# STMF4VE.net
KiCad netlist of a schematic drawn in Altium Designer
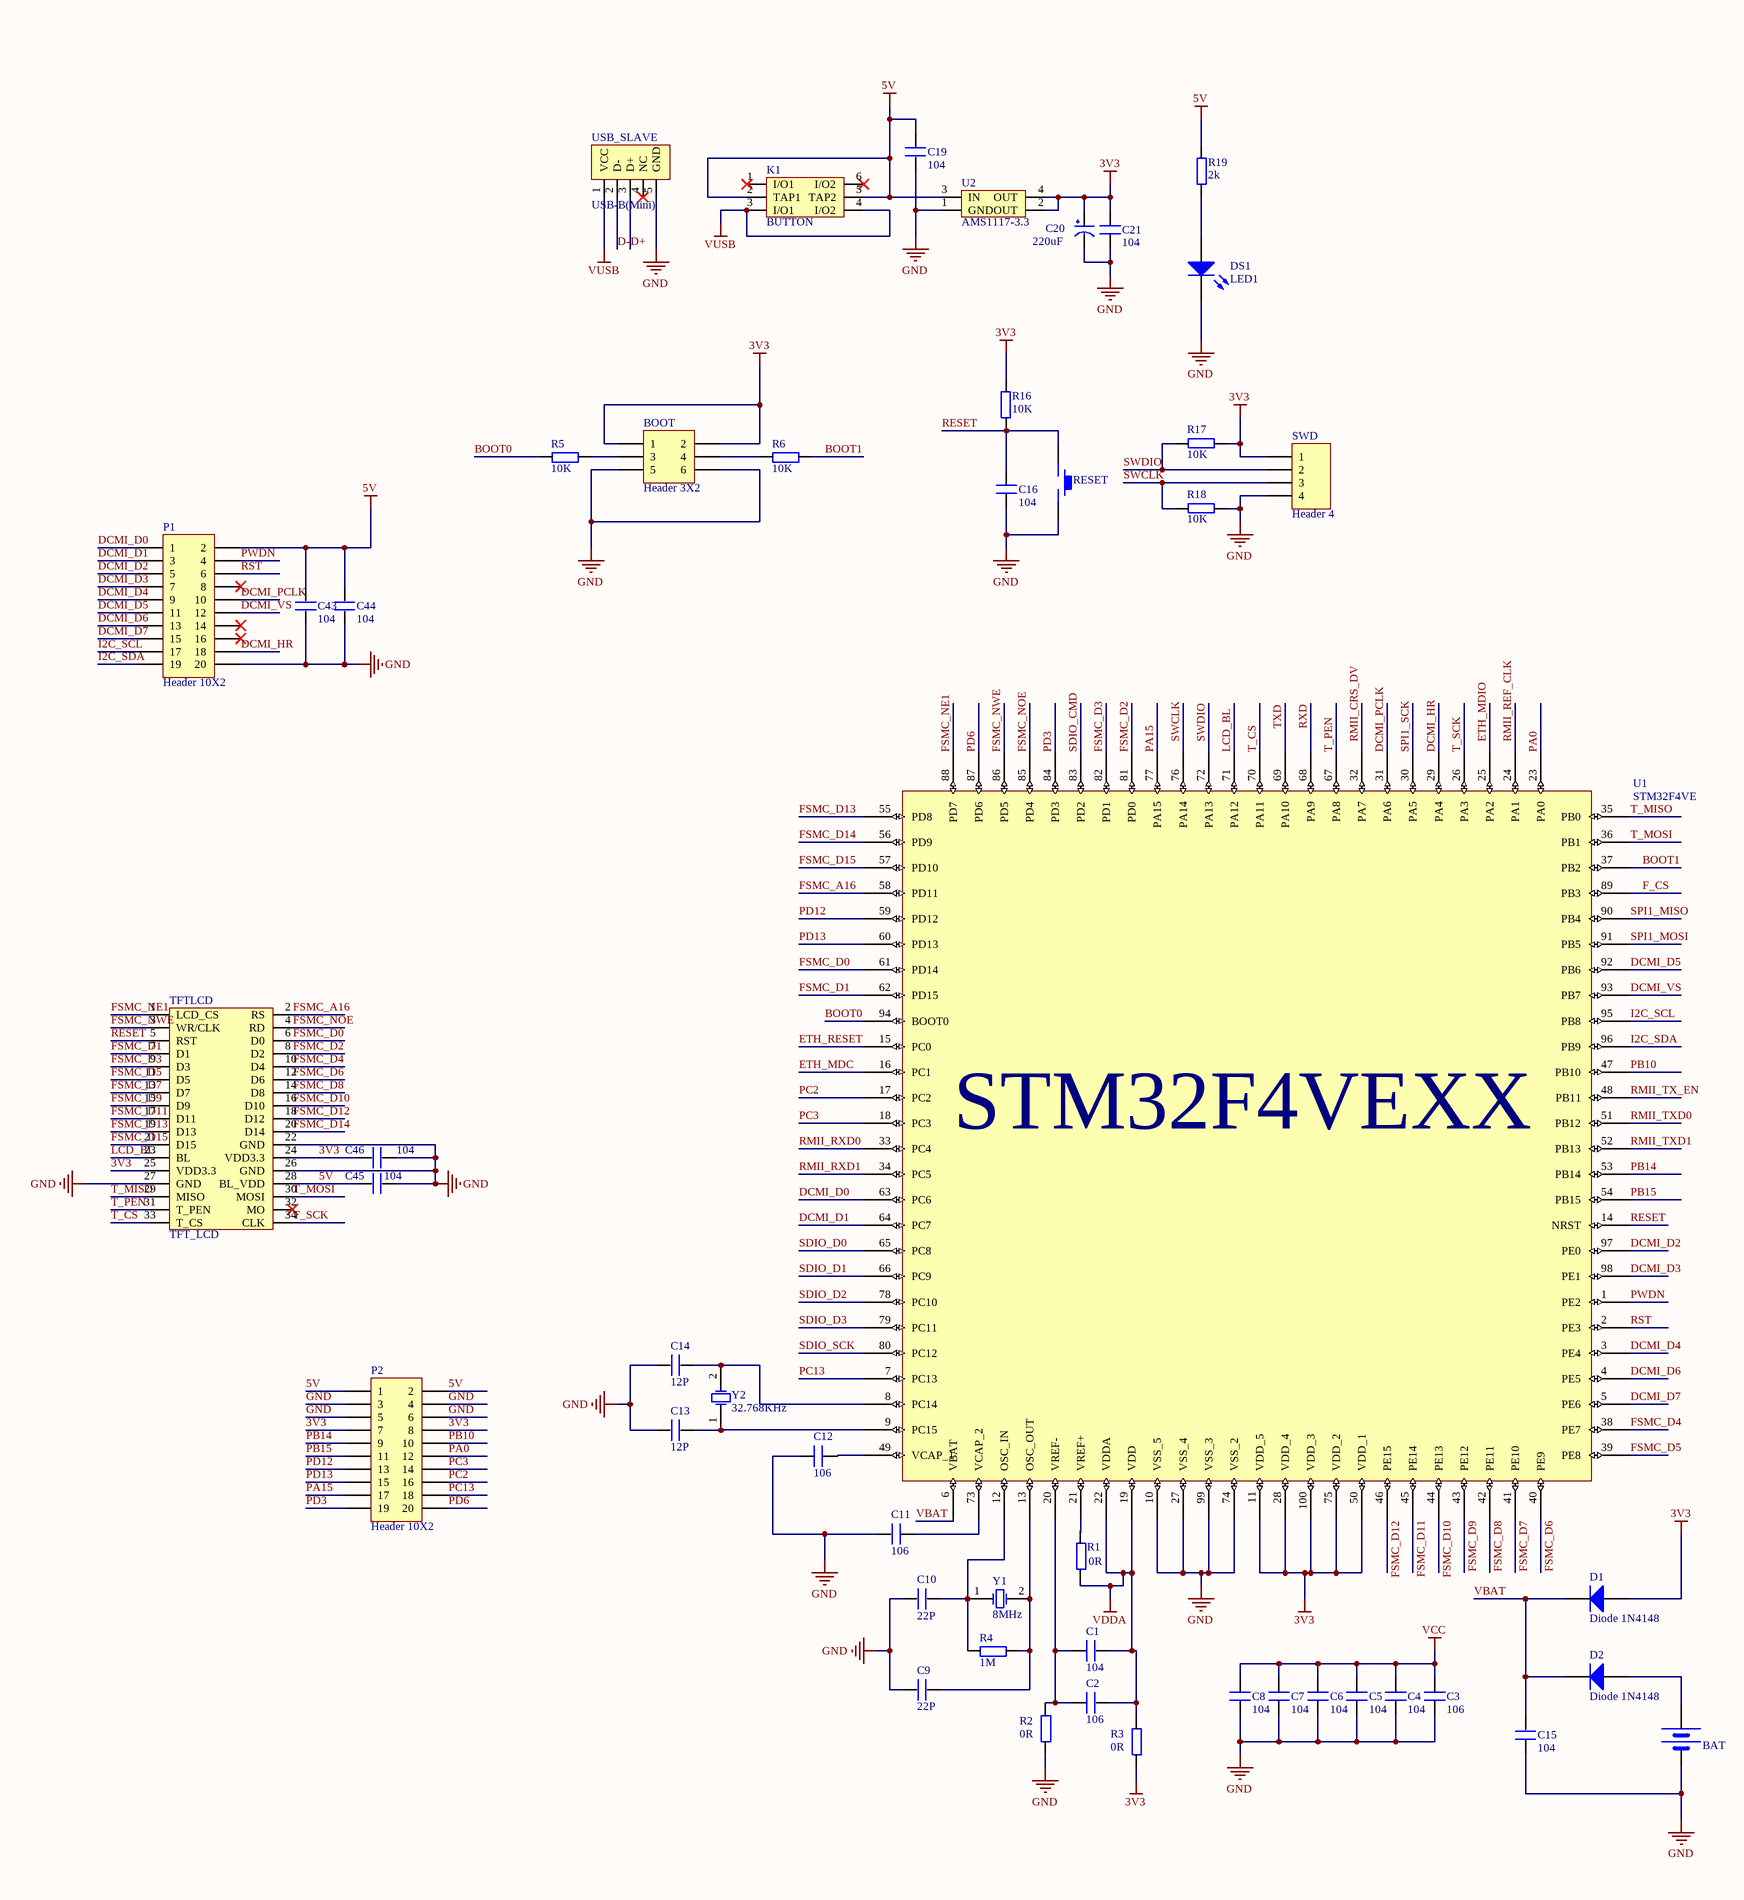
[diagram p0: STMF4VE.SchDoc, left]
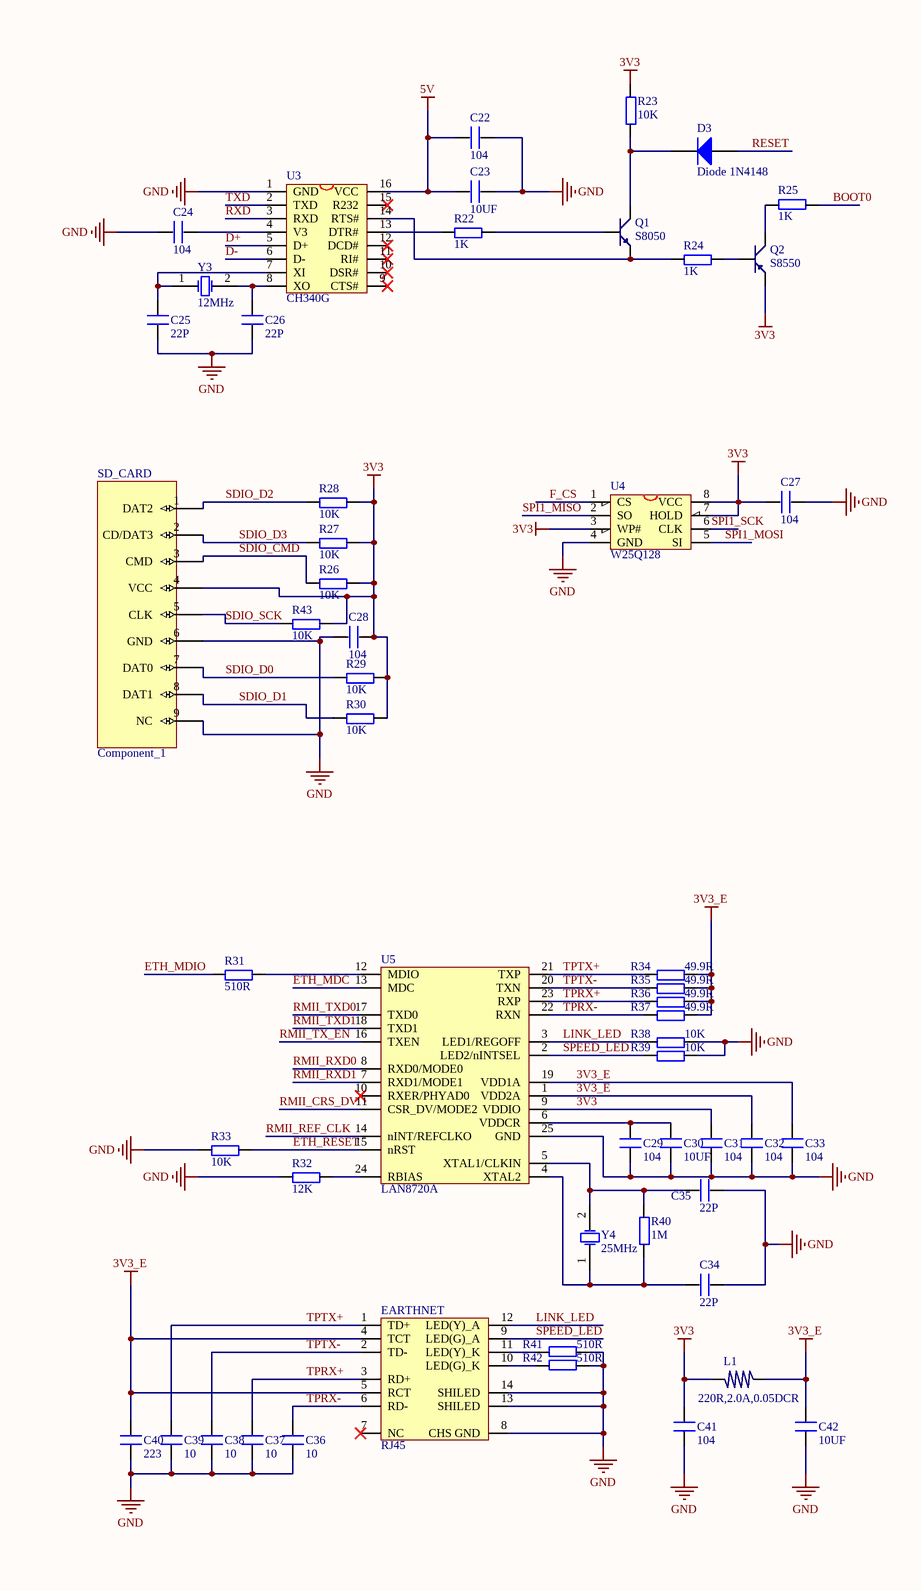
[diagram p1: STMF4VE.SchDoc, right]

(export (version "E")
  (design (tool "Eeschema 10.0.6"))
  (components
    (comp (ref "BAT")
      (value "BATT")
      (footprint "BATM")
      (libsource (lib "altium-import") (part "root_0_BAT_"))
    )
    (comp (ref "BOOT")
      (value "Header 3X2")
      (footprint "HDR2X3")
      (description "Header, 3-Pin, Dual row")
      (fields (field (name "PUBLISHER") "Altium Limited"))
      (libsource (lib "Explorer STM32F407封装库") (part "Header 3X2"))
    )
    (comp (ref "C1") (value "104") (footprint "0603P") (libsource (lib "altium-import") (part "root_0_C_")))
    (comp (ref "C2") (value "106") (footprint "0805") (libsource (lib "altium-import") (part "root_0_C_")))
    (comp (ref "C3") (value "106") (footprint "0805") (libsource (lib "Explorer STM32F407封装库") (part "C")))
    (comp (ref "C4") (value "104") (footprint "0603P") (libsource (lib "Explorer STM32F407封装库") (part "C")))
    (comp (ref "C5") (value "104") (footprint "0603P") (libsource (lib "Explorer STM32F407封装库") (part "C")))
    (comp (ref "C6") (value "104") (footprint "0603P") (libsource (lib "Explorer STM32F407封装库") (part "C")))
    (comp (ref "C7") (value "104") (footprint "0603P") (libsource (lib "Explorer STM32F407封装库") (part "C")))
    (comp (ref "C8") (value "104") (footprint "0603P") (libsource (lib "Explorer STM32F407封装库") (part "C")))
    (comp (ref "C9") (value "22P") (footprint "0603P") (libsource (lib "Explorer STM32F407封装库") (part "C")))
    (comp (ref "C10") (value "22P") (footprint "0603P") (libsource (lib "Explorer STM32F407封装库") (part "C")))
    (comp (ref "C11") (value "106") (footprint "0603P") (libsource (lib "Explorer STM32F407封装库") (part "C")))
    (comp (ref "C12") (value "106") (footprint "0603P") (libsource (lib "Explorer STM32F407封装库") (part "C")))
    (comp (ref "C13") (value "12P") (footprint "0603P") (libsource (lib "Explorer STM32F407封装库") (part "C")))
    (comp (ref "C14") (value "12P") (footprint "0603P") (libsource (lib "Explorer STM32F407封装库") (part "C")))
    (comp (ref "C15") (value "104") (footprint "0603P") (libsource (lib "altium-import") (part "root_1_C_")))
    (comp (ref "C16") (value "104") (footprint "0603P") (libsource (lib "Explorer STM32F407封装库") (part "C")))
    (comp (ref "C19") (value "104") (footprint "0603P") (libsource (lib "Explorer STM32F407封装库") (part "C")))
    (comp (ref "C20")
      (value "220uF")
      (footprint "CC6.56.5")
      (libsource (lib "Explorer STM32F407封装库") (part "CAP"))
    )
    (comp (ref "C21") (value "104") (footprint "0603P") (libsource (lib "Explorer STM32F407封装库") (part "C")))
    (comp (ref "C22") (value "104") (footprint "0603P") (libsource (lib "Explorer STM32F407封装库") (part "C")))
    (comp (ref "C23") (value "10UF") (footprint "0603P") (libsource (lib "Explorer STM32F407封装库") (part "C")))
    (comp (ref "C24") (value "104") (footprint "0603P") (libsource (lib "Explorer STM32F407封装库") (part "C")))
    (comp (ref "C25") (value "22P") (footprint "0603P") (libsource (lib "Explorer STM32F407封装库") (part "C")))
    (comp (ref "C26") (value "22P") (footprint "0603P") (libsource (lib "Explorer STM32F407封装库") (part "C")))
    (comp (ref "C27") (value "104") (footprint "0603P") (libsource (lib "Explorer STM32F407封装库") (part "C")))
    (comp (ref "C28") (value "104") (footprint "0603P") (libsource (lib "Explorer STM32F407封装库") (part "C")))
    (comp (ref "C29") (value "104") (footprint "0603P") (libsource (lib "Explorer STM32F407封装库") (part "C")))
    (comp (ref "C30") (value "10UF") (footprint "0603P") (libsource (lib "Explorer STM32F407封装库") (part "C")))
    (comp (ref "C31") (value "104") (footprint "0603P") (libsource (lib "Explorer STM32F407封装库") (part "C")))
    (comp (ref "C32") (value "104") (footprint "0603P") (libsource (lib "Explorer STM32F407封装库") (part "C")))
    (comp (ref "C33") (value "104") (footprint "0603P") (libsource (lib "Explorer STM32F407封装库") (part "C")))
    (comp (ref "C34") (value "22P") (footprint "0603P") (libsource (lib "Explorer STM32F407封装库") (part "C")))
    (comp (ref "C35") (value "22P") (footprint "0603P") (libsource (lib "Explorer STM32F407封装库") (part "C")))
    (comp (ref "C36") (value "10") (footprint "0603P") (libsource (lib "Explorer STM32F407封装库") (part "C")))
    (comp (ref "C37") (value "10") (footprint "0603P") (libsource (lib "Explorer STM32F407封装库") (part "C")))
    (comp (ref "C38") (value "10") (footprint "0603P") (libsource (lib "Explorer STM32F407封装库") (part "C")))
    (comp (ref "C39") (value "10") (footprint "0603P") (libsource (lib "Explorer STM32F407封装库") (part "C")))
    (comp (ref "C40") (value "223") (footprint "0603P") (libsource (lib "Explorer STM32F407封装库") (part "C")))
    (comp (ref "C41") (value "104") (footprint "0603P") (libsource (lib "Explorer STM32F407封装库") (part "C")))
    (comp (ref "C42") (value "10UF") (footprint "0603P") (libsource (lib "Explorer STM32F407封装库") (part "C")))
    (comp (ref "C43") (value "104") (footprint "0603P") (libsource (lib "Explorer STM32F407封装库") (part "C")))
    (comp (ref "C44") (value "104") (footprint "0603P") (libsource (lib "Explorer STM32F407封装库") (part "C")))
    (comp (ref "C45") (value "104") (footprint "0603P") (libsource (lib "Explorer STM32F407封装库") (part "C")))
    (comp (ref "C46") (value "104") (footprint "0603P") (libsource (lib "Explorer STM32F407封装库") (part "C")))
    (comp (ref "D1")
      (value "Diode 1N4148")
      (footprint "DO-35")
      (description "High Conductance Fast Diode")
      (fields (field (name "PUBLISHER") "Altium Limited"))
      (libsource (lib "Miscellaneous Devices") (part "Diode 1N4148"))
    )
    (comp (ref "D2")
      (value "Diode 1N4148")
      (footprint "DO-35")
      (description "High Conductance Fast Diode")
      (fields (field (name "PUBLISHER") "Altium Limited"))
      (libsource (lib "Miscellaneous Devices") (part "Diode 1N4148"))
    )
    (comp (ref "D3")
      (value "Diode 1N4148")
      (footprint "DO-35")
      (description "High Conductance Fast Diode")
      (fields (field (name "PUBLISHER") "Altium Limited"))
      (libsource (lib "Miscellaneous Devices") (part "Diode 1N4148"))
    )
    (comp (ref "DS1")
      (value "LED1")
      (footprint "SMDLED")
      (description "Typical RED, GREEN, YELLOW, AMBER GaAs LED")
      (fields (field (name "PUBLISHER") "Altium Limited"))
      (libsource (lib "Explorer STM32F407封装库") (part "LED2"))
    )
    (comp (ref "EARTHNET")
      (value "RJ45")
      (footprint "HR911105A")
      (libsource (lib "Explorer STM32F407封装库") (part "HR911105"))
    )
    (comp (ref "K1")
      (value "BUTTON")
      (footprint "BTN8.5*8.5")
      (libsource (lib "Explorer STM32F407封装库") (part "BUTTON"))
    )
    (comp (ref "L1")
      (value "220R,2.0A,0.05DCR")
      (footprint "0603P")
      (libsource (lib "Explorer STM32F407封装库") (part "L"))
    )
    (comp (ref "P1")
      (value "Header 10X2")
      (footprint "HDR2X10")
      (description "Header, 10-Pin, Dual row")
      (fields (field (name "PUBLISHER") "Altium Limited"))
      (libsource (lib "Miscellaneous Connectors") (part "Header 10X2"))
    )
    (comp (ref "P2")
      (value "Header 10X2")
      (footprint "HDR2X10")
      (description "Header, 10-Pin, Dual row")
      (fields (field (name "PUBLISHER") "Altium Limited"))
      (libsource (lib "Miscellaneous Connectors") (part "Header 10X2"))
    )
    (comp (ref "Q1")
      (value "S8050")
      (footprint "SOT-23R")
      (description "8050/BCW846/BCW847")
      (libsource (lib "Explorer STM32F407封装库") (part "NPN"))
    )
    (comp (ref "Q2")
      (value "S8550")
      (footprint "SOT-23R")
      (description "8550/BCW68")
      (libsource (lib "Explorer STM32F407封装库") (part "PNP"))
    )
    (comp (ref "R1") (value "0R") (footprint "0603P") (libsource (lib "altium-import") (part "root_1_R_")))
    (comp (ref "R2") (value "0R") (footprint "0603P") (libsource (lib "altium-import") (part "root_1_R_")))
    (comp (ref "R3") (value "0R") (footprint "0603P") (libsource (lib "altium-import") (part "root_1_R_")))
    (comp (ref "R4") (value "1M") (footprint "0603P") (libsource (lib "altium-import") (part "root_0_R_")))
    (comp (ref "R5") (value "10K") (footprint "0603P") (libsource (lib "Explorer STM32F407封装库") (part "R")))
    (comp (ref "R6") (value "10K") (footprint "0603P") (libsource (lib "Explorer STM32F407封装库") (part "R")))
    (comp (ref "R16") (value "10K") (footprint "0603P") (libsource (lib "Explorer STM32F407封装库") (part "R")))
    (comp (ref "R17") (value "10K") (footprint "0603P") (libsource (lib "Explorer STM32F407封装库") (part "R")))
    (comp (ref "R18") (value "10K") (footprint "0603P") (libsource (lib "Explorer STM32F407封装库") (part "R")))
    (comp (ref "R19") (value "2k") (footprint "0603P") (libsource (lib "Explorer STM32F407封装库") (part "R")))
    (comp (ref "R22") (value "1K") (footprint "0603P") (libsource (lib "Explorer STM32F407封装库") (part "R")))
    (comp (ref "R23") (value "10K") (footprint "0603P") (libsource (lib "Explorer STM32F407封装库") (part "R")))
    (comp (ref "R24") (value "1K") (footprint "0603P") (libsource (lib "Explorer STM32F407封装库") (part "R")))
    (comp (ref "R25") (value "1K") (footprint "0603P") (libsource (lib "Explorer STM32F407封装库") (part "R")))
    (comp (ref "R26") (value "10K") (footprint "0603P") (libsource (lib "Explorer STM32F407封装库") (part "R")))
    (comp (ref "R27") (value "10K") (footprint "0603P") (libsource (lib "Explorer STM32F407封装库") (part "R")))
    (comp (ref "R28") (value "10K") (footprint "0603P") (libsource (lib "Explorer STM32F407封装库") (part "R")))
    (comp (ref "R29") (value "10K") (footprint "0603P") (libsource (lib "Explorer STM32F407封装库") (part "R")))
    (comp (ref "R30") (value "10K") (footprint "0603P") (libsource (lib "Explorer STM32F407封装库") (part "R")))
    (comp (ref "R31") (value "510R") (footprint "0603P") (libsource (lib "Explorer STM32F407封装库") (part "R")))
    (comp (ref "R32") (value "12K") (footprint "0603P") (libsource (lib "Explorer STM32F407封装库") (part "R")))
    (comp (ref "R33") (value "10K") (footprint "0603P") (libsource (lib "Explorer STM32F407封装库") (part "R")))
    (comp (ref "R34")
      (value "49.9R")
      (footprint "0603P")
      (libsource (lib "Explorer STM32F407封装库") (part "R"))
    )
    (comp (ref "R35")
      (value "49.9R")
      (footprint "0603P")
      (libsource (lib "Explorer STM32F407封装库") (part "R"))
    )
    (comp (ref "R36")
      (value "49.9R")
      (footprint "0603P")
      (libsource (lib "Explorer STM32F407封装库") (part "R"))
    )
    (comp (ref "R37")
      (value "49.9R")
      (footprint "0603P")
      (libsource (lib "Explorer STM32F407封装库") (part "R"))
    )
    (comp (ref "R38") (value "10K") (footprint "0603P") (libsource (lib "Explorer STM32F407封装库") (part "R")))
    (comp (ref "R39") (value "10K") (footprint "0603P") (libsource (lib "Explorer STM32F407封装库") (part "R")))
    (comp (ref "R40") (value "1M") (footprint "0603P") (libsource (lib "Explorer STM32F407封装库") (part "R")))
    (comp (ref "R41") (value "510R") (footprint "0603P") (libsource (lib "Explorer STM32F407封装库") (part "R")))
    (comp (ref "R42") (value "510R") (footprint "0603P") (libsource (lib "Explorer STM32F407封装库") (part "R")))
    (comp (ref "R43") (value "10K") (footprint "0603P") (libsource (lib "Explorer STM32F407封装库") (part "R")))
    (comp (ref "RESET")
      (value "KEY_M")
      (footprint "KEY_M")
      (libsource (lib "Explorer STM32F407封装库") (part "KEY_M"))
    )
    (comp (ref "SD_CARD")
      (value "Component_1")
      (footprint "TF_SD")
      (libsource (lib "TF_SD") (part "Component_1"))
    )
    (comp (ref "SWD")
      (value "Header 4")
      (footprint "HDR1X4")
      (description "Header, 4-Pin")
      (fields (field (name "PUBLISHER") "Altium Limited"))
      (libsource (lib "Explorer STM32F407封装库") (part "Header 4"))
    )
    (comp (ref "TFTLCD")
      (value "TFT_LCD")
      (footprint "TFT_LCD")
      (libsource (lib "Explorer STM32F407封装库") (part "TFT_LCD"))
    )
    (comp (ref "U1")
      (value "STM32F4VE")
      (footprint "LQFP100")
      (libsource (lib "stm32F4VE") (part "STM32F4VE"))
    )
    (comp (ref "U2")
      (value "AMS1117-3.3")
      (footprint "AMS1117")
      (libsource (lib "Explorer STM32F407封装库") (part "AMS1117"))
    )
    (comp (ref "U3")
      (value "CH340G")
      (footprint "SOP16M")
      (description "USB2UART")
      (libsource (lib "Explorer STM32F407封装库") (part "CH340G"))
    )
    (comp (ref "U4")
      (value "W25Q128")
      (footprint "SOIC-8")
      (description "W25X16;SST25VF016;MX25L1605")
      (libsource (lib "Explorer STM32F407封装库") (part "W25X16"))
    )
    (comp (ref "U5")
      (value "LAN8720A")
      (footprint "QFN24")
      (description "ETH PHY")
      (libsource (lib "Explorer STM32F407封装库") (part "LAN8720"))
    )
    (comp (ref "USB_SLAVE")
      (value "USB-B(Mini)")
      (footprint "USB/SM0.8-6H5")
      (libsource (lib "Explorer STM32F407封装库") (part "USB5"))
    )
    (comp (ref "Y1")
      (value "8MHz")
      (footprint "49S_SMD")
      (description "Crystal Oscillator")
      (fields (field (name "PUBLISHER") "Altium Limited"))
      (libsource (lib "altium-import") (part "root_0_XTAL_"))
    )
    (comp (ref "Y2")
      (value "32.768KHz")
      (footprint "JZ32768")
      (description "Crystal Oscillator")
      (fields (field (name "PUBLISHER") "Altium Limited"))
      (libsource (lib "Explorer STM32F407封装库") (part "XTAL"))
    )
    (comp (ref "Y3")
      (value "12MHz")
      (footprint "49S_SMD")
      (description "Crystal Oscillator")
      (fields (field (name "PUBLISHER") "Altium Limited"))
      (libsource (lib "Explorer STM32F407封装库") (part "XTAL"))
    )
    (comp (ref "Y4")
      (value "25MHz")
      (footprint "49S_SMD")
      (description "Crystal Oscillator")
      (fields (field (name "PUBLISHER") "Altium Limited"))
      (libsource (lib "Explorer STM32F407封装库") (part "XTAL"))
    )
  )
  (nets
    (net (code "1") (name "/BOOT0") (class "Default")
      (node (ref "R25") (pin "1") (pintype "passive"))
      (node (ref "R5") (pin "1") (pintype "passive"))
      (node (ref "U1") (pin "94") (pinfunction "BOOT0_94") (pintype "bidirectional"))
    )
    (net (code "2") (name "/BOOT1") (class "Default")
      (node (ref "R6") (pin "2") (pintype "passive"))
      (node (ref "U1") (pin "37") (pinfunction "PB2_37") (pintype "bidirectional"))
    )
    (net (code "3") (name "/D+") (class "Default")
      (node (ref "U3") (pin "5") (pinfunction "D+_5") (pintype "passive"))
      (node (ref "USB_SLAVE") (pin "3") (pinfunction "D+_3") (pintype "passive"))
    )
    (net (code "4") (name "/D-") (class "Default")
      (node (ref "U3") (pin "6") (pinfunction "D-_6") (pintype "passive"))
      (node (ref "USB_SLAVE") (pin "2") (pinfunction "D-_2") (pintype "passive"))
    )
    (net (code "5") (name "/DCMI_D0") (class "Default")
      (node (ref "P1") (pin "1") (pinfunction "1_1") (pintype "passive"))
      (node (ref "U1") (pin "63") (pinfunction "PC6_63") (pintype "bidirectional"))
    )
    (net (code "6") (name "/DCMI_D1") (class "Default")
      (node (ref "P1") (pin "3") (pinfunction "3_3") (pintype "passive"))
      (node (ref "U1") (pin "64") (pinfunction "PC7_64") (pintype "bidirectional"))
    )
    (net (code "7") (name "/DCMI_D2") (class "Default")
      (node (ref "P1") (pin "5") (pinfunction "5_5") (pintype "passive"))
      (node (ref "U1") (pin "97") (pinfunction "PE0_97") (pintype "bidirectional"))
    )
    (net (code "8") (name "/DCMI_D3") (class "Default")
      (node (ref "P1") (pin "7") (pinfunction "7_7") (pintype "passive"))
      (node (ref "U1") (pin "98") (pinfunction "PE1_98") (pintype "bidirectional"))
    )
    (net (code "9") (name "/DCMI_D4") (class "Default")
      (node (ref "P1") (pin "9") (pinfunction "9_9") (pintype "passive"))
      (node (ref "U1") (pin "3") (pinfunction "PE4_3") (pintype "bidirectional"))
    )
    (net (code "10") (name "/DCMI_D5") (class "Default")
      (node (ref "P1") (pin "11") (pinfunction "11_11") (pintype "passive"))
      (node (ref "U1") (pin "92") (pinfunction "PB6_92") (pintype "bidirectional"))
    )
    (net (code "11") (name "/DCMI_D6") (class "Default")
      (node (ref "P1") (pin "13") (pinfunction "13_13") (pintype "passive"))
      (node (ref "U1") (pin "4") (pinfunction "PE5_4") (pintype "bidirectional"))
    )
    (net (code "12") (name "/DCMI_D7") (class "Default")
      (node (ref "P1") (pin "15") (pinfunction "15_15") (pintype "passive"))
      (node (ref "U1") (pin "5") (pinfunction "PE6_5") (pintype "bidirectional"))
    )
    (net (code "13") (name "/DCMI_HR") (class "Default")
      (node (ref "P1") (pin "18") (pinfunction "18_18") (pintype "passive"))
      (node (ref "U1") (pin "29") (pinfunction "PA4_29") (pintype "bidirectional"))
    )
    (net (code "14") (name "/DCMI_PCLK") (class "Default")
      (node (ref "P1") (pin "10") (pinfunction "10_10") (pintype "passive"))
      (node (ref "U1") (pin "31") (pinfunction "PA6_31") (pintype "bidirectional"))
    )
    (net (code "15") (name "/DCMI_VS") (class "Default")
      (node (ref "P1") (pin "12") (pinfunction "12_12") (pintype "passive"))
      (node (ref "U1") (pin "93") (pinfunction "PB7_93") (pintype "bidirectional"))
    )
    (net (code "16") (name "/ETH_MDC") (class "Default")
      (node (ref "U1") (pin "16") (pinfunction "PC1_16") (pintype "bidirectional"))
      (node (ref "U5") (pin "13") (pinfunction "MDC_13") (pintype "passive"))
    )
    (net (code "17") (name "/ETH_MDIO") (class "Default")
      (node (ref "R31") (pin "1") (pintype "passive"))
      (node (ref "U1") (pin "25") (pinfunction "PA2_25") (pintype "bidirectional"))
    )
    (net (code "18") (name "/ETH_RESET") (class "Default")
      (node (ref "R33") (pin "2") (pintype "passive"))
      (node (ref "U1") (pin "15") (pinfunction "PC0_15") (pintype "bidirectional"))
      (node (ref "U5") (pin "15") (pinfunction "nRST_15") (pintype "passive"))
    )
    (net (code "19") (name "/FSMC_A16") (class "Default")
      (node (ref "TFTLCD") (pin "2") (pinfunction "RS_2") (pintype "passive"))
      (node (ref "U1") (pin "58") (pinfunction "PD11_58") (pintype "bidirectional"))
    )
    (net (code "20") (name "/FSMC_D0") (class "Default")
      (node (ref "TFTLCD") (pin "6") (pinfunction "D0_6") (pintype "passive"))
      (node (ref "U1") (pin "61") (pinfunction "PD14_61") (pintype "bidirectional"))
    )
    (net (code "21") (name "/FSMC_D1") (class "Default")
      (node (ref "TFTLCD") (pin "7") (pinfunction "D1_7") (pintype "passive"))
      (node (ref "U1") (pin "62") (pinfunction "PD15_62") (pintype "bidirectional"))
    )
    (net (code "22") (name "/FSMC_D2") (class "Default")
      (node (ref "TFTLCD") (pin "8") (pinfunction "D2_8") (pintype "passive"))
      (node (ref "U1") (pin "81") (pinfunction "PD0_81") (pintype "bidirectional"))
    )
    (net (code "23") (name "/FSMC_D3") (class "Default")
      (node (ref "TFTLCD") (pin "9") (pinfunction "D3_9") (pintype "passive"))
      (node (ref "U1") (pin "82") (pinfunction "PD1_82") (pintype "bidirectional"))
    )
    (net (code "24") (name "/FSMC_D4") (class "Default")
      (node (ref "TFTLCD") (pin "10") (pinfunction "D4_10") (pintype "passive"))
      (node (ref "U1") (pin "38") (pinfunction "PE7_38") (pintype "bidirectional"))
    )
    (net (code "25") (name "/FSMC_D5") (class "Default")
      (node (ref "TFTLCD") (pin "11") (pinfunction "D5_11") (pintype "passive"))
      (node (ref "U1") (pin "39") (pinfunction "PE8_39") (pintype "bidirectional"))
    )
    (net (code "26") (name "/FSMC_D6") (class "Default")
      (node (ref "TFTLCD") (pin "12") (pinfunction "D6_12") (pintype "passive"))
      (node (ref "U1") (pin "40") (pinfunction "PE9_40") (pintype "bidirectional"))
    )
    (net (code "27") (name "/FSMC_D7") (class "Default")
      (node (ref "TFTLCD") (pin "13") (pinfunction "D7_13") (pintype "passive"))
      (node (ref "U1") (pin "41") (pinfunction "PE10_41") (pintype "bidirectional"))
    )
    (net (code "28") (name "/FSMC_D8") (class "Default")
      (node (ref "TFTLCD") (pin "14") (pinfunction "D8_14") (pintype "passive"))
      (node (ref "U1") (pin "42") (pinfunction "PE11_42") (pintype "bidirectional"))
    )
    (net (code "29") (name "/FSMC_D9") (class "Default")
      (node (ref "TFTLCD") (pin "15") (pinfunction "D9_15") (pintype "passive"))
      (node (ref "U1") (pin "43") (pinfunction "PE12_43") (pintype "bidirectional"))
    )
    (net (code "30") (name "/FSMC_D10") (class "Default")
      (node (ref "TFTLCD") (pin "16") (pinfunction "D10_16") (pintype "passive"))
      (node (ref "U1") (pin "44") (pinfunction "PE13_44") (pintype "bidirectional"))
    )
    (net (code "31") (name "/FSMC_D11") (class "Default")
      (node (ref "TFTLCD") (pin "17") (pinfunction "D11_17") (pintype "passive"))
      (node (ref "U1") (pin "45") (pinfunction "PE14_45") (pintype "bidirectional"))
    )
    (net (code "32") (name "/FSMC_D12") (class "Default")
      (node (ref "TFTLCD") (pin "18") (pinfunction "D12_18") (pintype "passive"))
      (node (ref "U1") (pin "46") (pinfunction "PE15_46") (pintype "bidirectional"))
    )
    (net (code "33") (name "/FSMC_D13") (class "Default")
      (node (ref "TFTLCD") (pin "19") (pinfunction "D13_19") (pintype "passive"))
      (node (ref "U1") (pin "55") (pinfunction "PD8_55") (pintype "bidirectional"))
    )
    (net (code "34") (name "/FSMC_D14") (class "Default")
      (node (ref "TFTLCD") (pin "20") (pinfunction "D14_20") (pintype "passive"))
      (node (ref "U1") (pin "56") (pinfunction "PD9_56") (pintype "bidirectional"))
    )
    (net (code "35") (name "/FSMC_D15") (class "Default")
      (node (ref "TFTLCD") (pin "21") (pinfunction "D15_21") (pintype "passive"))
      (node (ref "U1") (pin "57") (pinfunction "PD10_57") (pintype "bidirectional"))
    )
    (net (code "36") (name "/FSMC_NE1") (class "Default")
      (node (ref "TFTLCD") (pin "1") (pinfunction "LCD_CS_1") (pintype "passive"))
      (node (ref "U1") (pin "88") (pinfunction "PD7_88") (pintype "bidirectional"))
    )
    (net (code "37") (name "/FSMC_NOE") (class "Default")
      (node (ref "TFTLCD") (pin "4") (pinfunction "RD_4") (pintype "passive"))
      (node (ref "U1") (pin "85") (pinfunction "PD4_85") (pintype "bidirectional"))
    )
    (net (code "38") (name "/FSMC_NWE") (class "Default")
      (node (ref "TFTLCD") (pin "3") (pinfunction "WR/CLK_3") (pintype "passive"))
      (node (ref "U1") (pin "86") (pinfunction "PD5_86") (pintype "bidirectional"))
    )
    (net (code "39") (name "/F_CS") (class "Default")
      (node (ref "U1") (pin "89") (pinfunction "PB3_89") (pintype "bidirectional"))
      (node (ref "U4") (pin "1") (pinfunction "CS_1") (pintype "passive"))
    )
    (net (code "40") (name "/I2C_SCL") (class "Default")
      (node (ref "P1") (pin "17") (pinfunction "17_17") (pintype "passive"))
      (node (ref "U1") (pin "95") (pinfunction "PB8_95") (pintype "bidirectional"))
    )
    (net (code "41") (name "/I2C_SDA") (class "Default")
      (node (ref "P1") (pin "19") (pinfunction "19_19") (pintype "passive"))
      (node (ref "U1") (pin "96") (pinfunction "PB9_96") (pintype "bidirectional"))
    )
    (net (code "42") (name "/LCD_BL") (class "Default")
      (node (ref "TFTLCD") (pin "23") (pinfunction "BL_23") (pintype "passive"))
      (node (ref "U1") (pin "71") (pinfunction "PA12_71") (pintype "bidirectional"))
    )
    (net (code "43") (name "/LINK_LED") (class "Default")
      (node (ref "EARTHNET") (pin "12") (pinfunction "LED(Y)_A_12") (pintype "passive"))
      (node (ref "R38") (pin "1") (pintype "passive"))
      (node (ref "U5") (pin "3") (pinfunction "LED1/REGOFF_3") (pintype "passive"))
    )
    (net (code "44") (name "/PA0") (class "Default")
      (node (ref "P2") (pin "12") (pinfunction "12_12") (pintype "passive"))
      (node (ref "U1") (pin "23") (pinfunction "PA0_23") (pintype "bidirectional"))
    )
    (net (code "45") (name "/PA15") (class "Default")
      (node (ref "P2") (pin "17") (pinfunction "17_17") (pintype "passive"))
      (node (ref "U1") (pin "77") (pinfunction "PA15_77") (pintype "bidirectional"))
    )
    (net (code "46") (name "/PB10") (class "Default")
      (node (ref "P2") (pin "10") (pinfunction "10_10") (pintype "passive"))
      (node (ref "U1") (pin "47") (pinfunction "PB10_47") (pintype "bidirectional"))
    )
    (net (code "47") (name "/PB14") (class "Default")
      (node (ref "P2") (pin "9") (pinfunction "9_9") (pintype "passive"))
      (node (ref "U1") (pin "53") (pinfunction "PB14_53") (pintype "bidirectional"))
    )
    (net (code "48") (name "/PB15") (class "Default")
      (node (ref "P2") (pin "11") (pinfunction "11_11") (pintype "passive"))
      (node (ref "U1") (pin "54") (pinfunction "PB15_54") (pintype "bidirectional"))
    )
    (net (code "49") (name "/PC2") (class "Default")
      (node (ref "P2") (pin "16") (pinfunction "16_16") (pintype "passive"))
      (node (ref "U1") (pin "17") (pinfunction "PC2_17") (pintype "bidirectional"))
    )
    (net (code "50") (name "/PC3") (class "Default")
      (node (ref "P2") (pin "14") (pinfunction "14_14") (pintype "passive"))
      (node (ref "U1") (pin "18") (pinfunction "PC3_18") (pintype "bidirectional"))
    )
    (net (code "51") (name "/PC13") (class "Default")
      (node (ref "P2") (pin "18") (pinfunction "18_18") (pintype "passive"))
      (node (ref "U1") (pin "7") (pinfunction "PC13_7") (pintype "bidirectional"))
    )
    (net (code "52") (name "/PD3") (class "Default")
      (node (ref "P2") (pin "19") (pinfunction "19_19") (pintype "passive"))
      (node (ref "U1") (pin "84") (pinfunction "PD3_84") (pintype "bidirectional"))
    )
    (net (code "53") (name "/PD6") (class "Default")
      (node (ref "P2") (pin "20") (pinfunction "20_20") (pintype "passive"))
      (node (ref "U1") (pin "87") (pinfunction "PD6_87") (pintype "bidirectional"))
    )
    (net (code "54") (name "/PD12") (class "Default")
      (node (ref "P2") (pin "13") (pinfunction "13_13") (pintype "passive"))
      (node (ref "U1") (pin "59") (pinfunction "PD12_59") (pintype "bidirectional"))
    )
    (net (code "55") (name "/PD13") (class "Default")
      (node (ref "P2") (pin "15") (pinfunction "15_15") (pintype "passive"))
      (node (ref "U1") (pin "60") (pinfunction "PD13_60") (pintype "bidirectional"))
    )
    (net (code "56") (name "/PWDN") (class "Default")
      (node (ref "P1") (pin "4") (pinfunction "4_4") (pintype "passive"))
      (node (ref "U1") (pin "1") (pinfunction "PE2_1") (pintype "bidirectional"))
    )
    (net (code "57") (name "/RESET") (class "Default")
      (node (ref "C16") (pin "2") (pintype "passive"))
      (node (ref "D3") (pin "1") (pinfunction "A_1") (pintype "passive"))
      (node (ref "R16") (pin "2") (pintype "passive"))
      (node (ref "RESET") (pin "1") (pinfunction "1_1") (pintype "passive"))
      (node (ref "TFTLCD") (pin "5") (pinfunction "RST_5") (pintype "passive"))
      (node (ref "U1") (pin "14") (pinfunction "NRST_14") (pintype "bidirectional"))
    )
    (net (code "58") (name "/RMII_CRS_DV") (class "Default")
      (node (ref "U1") (pin "32") (pinfunction "PA7_32") (pintype "bidirectional"))
      (node (ref "U5") (pin "11") (pinfunction "CSR_DV/MODE2_11") (pintype "passive"))
    )
    (net (code "59") (name "/RMII_REF_CLK") (class "Default")
      (node (ref "U1") (pin "24") (pinfunction "PA1_24") (pintype "bidirectional"))
      (node (ref "U5") (pin "14") (pinfunction "nINT/REFCLKO_14") (pintype "passive"))
    )
    (net (code "60") (name "/RMII_RXD0") (class "Default")
      (node (ref "U1") (pin "33") (pinfunction "PC4_33") (pintype "bidirectional"))
      (node (ref "U5") (pin "8") (pinfunction "RXD0/MODE0_8") (pintype "passive"))
    )
    (net (code "61") (name "/RMII_RXD1") (class "Default")
      (node (ref "U1") (pin "34") (pinfunction "PC5_34") (pintype "bidirectional"))
      (node (ref "U5") (pin "7") (pinfunction "RXD1/MODE1_7") (pintype "passive"))
    )
    (net (code "62") (name "/RMII_TXD0") (class "Default")
      (node (ref "U1") (pin "51") (pinfunction "PB12_51") (pintype "bidirectional"))
      (node (ref "U5") (pin "17") (pinfunction "TXD0_17") (pintype "passive"))
    )
    (net (code "63") (name "/RMII_TXD1") (class "Default")
      (node (ref "U1") (pin "52") (pinfunction "PB13_52") (pintype "bidirectional"))
      (node (ref "U5") (pin "18") (pinfunction "TXD1_18") (pintype "passive"))
    )
    (net (code "64") (name "/RMII_TX_EN") (class "Default")
      (node (ref "U1") (pin "48") (pinfunction "PB11_48") (pintype "bidirectional"))
      (node (ref "U5") (pin "16") (pinfunction "TXEN_16") (pintype "passive"))
    )
    (net (code "65") (name "/RST") (class "Default")
      (node (ref "P1") (pin "6") (pinfunction "6_6") (pintype "passive"))
      (node (ref "U1") (pin "2") (pinfunction "PE3_2") (pintype "bidirectional"))
    )
    (net (code "66") (name "/RXD") (class "Default")
      (node (ref "U1") (pin "68") (pinfunction "PA9_68") (pintype "bidirectional"))
      (node (ref "U3") (pin "3") (pinfunction "RXD_3") (pintype "passive"))
    )
    (net (code "67") (name "/SDIO_CMD") (class "Default")
      (node (ref "R26") (pin "1") (pintype "passive"))
      (node (ref "SD_CARD") (pin "3") (pinfunction "CMD_3") (pintype "bidirectional"))
      (node (ref "U1") (pin "83") (pinfunction "PD2_83") (pintype "bidirectional"))
    )
    (net (code "68") (name "/SDIO_D0") (class "Default")
      (node (ref "R29") (pin "1") (pintype "passive"))
      (node (ref "SD_CARD") (pin "7") (pinfunction "DAT0_7") (pintype "bidirectional"))
      (node (ref "U1") (pin "65") (pinfunction "PC8_65") (pintype "bidirectional"))
    )
    (net (code "69") (name "/SDIO_D1") (class "Default")
      (node (ref "R30") (pin "1") (pintype "passive"))
      (node (ref "SD_CARD") (pin "8") (pinfunction "DAT1_8") (pintype "bidirectional"))
      (node (ref "U1") (pin "66") (pinfunction "PC9_66") (pintype "bidirectional"))
    )
    (net (code "70") (name "/SDIO_D2") (class "Default")
      (node (ref "R28") (pin "1") (pintype "passive"))
      (node (ref "SD_CARD") (pin "1") (pinfunction "DAT2_1") (pintype "bidirectional"))
      (node (ref "U1") (pin "78") (pinfunction "PC10_78") (pintype "bidirectional"))
    )
    (net (code "71") (name "/SDIO_D3") (class "Default")
      (node (ref "R27") (pin "1") (pintype "passive"))
      (node (ref "SD_CARD") (pin "2") (pinfunction "CD/DAT3_2") (pintype "bidirectional"))
      (node (ref "U1") (pin "79") (pinfunction "PC11_79") (pintype "bidirectional"))
    )
    (net (code "72") (name "/SDIO_SCK") (class "Default")
      (node (ref "R43") (pin "1") (pintype "passive"))
      (node (ref "SD_CARD") (pin "5") (pinfunction "CLK_5") (pintype "bidirectional"))
      (node (ref "U1") (pin "80") (pinfunction "PC12_80") (pintype "bidirectional"))
    )
    (net (code "73") (name "/SPEED_LED") (class "Default")
      (node (ref "EARTHNET") (pin "9") (pinfunction "LED(G)_A_9") (pintype "passive"))
      (node (ref "R39") (pin "1") (pintype "passive"))
      (node (ref "U5") (pin "2") (pinfunction "LED2/nINTSEL_2") (pintype "passive"))
    )
    (net (code "74") (name "/SPI1_MISO") (class "Default")
      (node (ref "U1") (pin "90") (pinfunction "PB4_90") (pintype "bidirectional"))
      (node (ref "U4") (pin "2") (pinfunction "SO_2") (pintype "passive"))
    )
    (net (code "75") (name "/SPI1_MOSI") (class "Default")
      (node (ref "U1") (pin "91") (pinfunction "PB5_91") (pintype "bidirectional"))
      (node (ref "U4") (pin "5") (pinfunction "SI_5") (pintype "passive"))
    )
    (net (code "76") (name "/SPI1_SCK") (class "Default")
      (node (ref "U1") (pin "30") (pinfunction "PA5_30") (pintype "bidirectional"))
      (node (ref "U4") (pin "6") (pinfunction "CLK_6") (pintype "passive"))
    )
    (net (code "77") (name "/SWCLK") (class "Default")
      (node (ref "R18") (pin "2") (pintype "passive"))
      (node (ref "SWD") (pin "3") (pinfunction "3_3") (pintype "passive"))
      (node (ref "U1") (pin "76") (pinfunction "PA14_76") (pintype "bidirectional"))
    )
    (net (code "78") (name "/SWDIO") (class "Default")
      (node (ref "R17") (pin "2") (pintype "passive"))
      (node (ref "SWD") (pin "2") (pinfunction "2_2") (pintype "passive"))
      (node (ref "U1") (pin "72") (pinfunction "PA13_72") (pintype "bidirectional"))
    )
    (net (code "79") (name "/TPRX+") (class "Default")
      (node (ref "C37") (pin "2") (pintype "passive"))
      (node (ref "EARTHNET") (pin "3") (pinfunction "RD+_3") (pintype "passive"))
      (node (ref "R36") (pin "1") (pintype "passive"))
      (node (ref "U5") (pin "23") (pinfunction "RXP_23") (pintype "passive"))
    )
    (net (code "80") (name "/TPRX-") (class "Default")
      (node (ref "C36") (pin "2") (pintype "passive"))
      (node (ref "EARTHNET") (pin "6") (pinfunction "RD-_6") (pintype "passive"))
      (node (ref "R37") (pin "1") (pintype "passive"))
      (node (ref "U5") (pin "22") (pinfunction "RXN_22") (pintype "passive"))
    )
    (net (code "81") (name "/TPTX+") (class "Default")
      (node (ref "C39") (pin "2") (pintype "passive"))
      (node (ref "EARTHNET") (pin "1") (pinfunction "TD+_1") (pintype "passive"))
      (node (ref "R34") (pin "1") (pintype "passive"))
      (node (ref "U5") (pin "21") (pinfunction "TXP_21") (pintype "passive"))
    )
    (net (code "82") (name "/TPTX-") (class "Default")
      (node (ref "C38") (pin "2") (pintype "passive"))
      (node (ref "EARTHNET") (pin "2") (pinfunction "TD-_2") (pintype "passive"))
      (node (ref "R35") (pin "1") (pintype "passive"))
      (node (ref "U5") (pin "20") (pinfunction "TXN_20") (pintype "passive"))
    )
    (net (code "83") (name "/TXD") (class "Default")
      (node (ref "U1") (pin "69") (pinfunction "PA10_69") (pintype "bidirectional"))
      (node (ref "U3") (pin "2") (pinfunction "TXD_2") (pintype "passive"))
    )
    (net (code "84") (name "/T_CS") (class "Default")
      (node (ref "TFTLCD") (pin "33") (pinfunction "T_CS_33") (pintype "passive"))
      (node (ref "U1") (pin "70") (pinfunction "PA11_70") (pintype "bidirectional"))
    )
    (net (code "85") (name "/T_MISO") (class "Default")
      (node (ref "TFTLCD") (pin "29") (pinfunction "MISO_29") (pintype "passive"))
      (node (ref "U1") (pin "35") (pinfunction "PB0_35") (pintype "bidirectional"))
    )
    (net (code "86") (name "/T_MOSI") (class "Default")
      (node (ref "TFTLCD") (pin "30") (pinfunction "MOSI_30") (pintype "passive"))
      (node (ref "U1") (pin "36") (pinfunction "PB1_36") (pintype "bidirectional"))
    )
    (net (code "87") (name "/T_PEN") (class "Default")
      (node (ref "TFTLCD") (pin "31") (pinfunction "T_PEN_31") (pintype "passive"))
      (node (ref "U1") (pin "67") (pinfunction "PA8_67") (pintype "bidirectional"))
    )
    (net (code "88") (name "/T_SCK") (class "Default")
      (node (ref "TFTLCD") (pin "34") (pinfunction "CLK_34") (pintype "passive"))
      (node (ref "U1") (pin "26") (pinfunction "PA3_26") (pintype "bidirectional"))
    )
    (net (code "89") (name "/VBAT") (class "Default")
      (node (ref "C15") (pin "2") (pintype "passive"))
      (node (ref "D1") (pin "2") (pinfunction "K_2") (pintype "passive"))
      (node (ref "D2") (pin "2") (pinfunction "K_2") (pintype "passive"))
      (node (ref "U1") (pin "6") (pinfunction "VBAT_6") (pintype "bidirectional"))
    )
    (net (code "90") (name "3V3") (class "Default")
      (node (ref "BOOT") (pin "1") (pinfunction "1_1") (pintype "passive"))
      (node (ref "BOOT") (pin "2") (pinfunction "2_2") (pintype "passive"))
      (node (ref "C20") (pin "1") (pinfunction "VCC_1") (pintype "passive"))
      (node (ref "C21") (pin "2") (pintype "passive"))
      (node (ref "C27") (pin "1") (pintype "passive"))
      (node (ref "C28") (pin "2") (pintype "passive"))
      (node (ref "C31") (pin "2") (pintype "passive"))
      (node (ref "C41") (pin "2") (pintype "passive"))
      (node (ref "C46") (pin "1") (pintype "passive"))
      (node (ref "D1") (pin "1") (pinfunction "A_1") (pintype "passive"))
      (node (ref "L1") (pin "2") (pintype "passive"))
      (node (ref "P2") (pin "7") (pinfunction "7_7") (pintype "passive"))
      (node (ref "P2") (pin "8") (pinfunction "8_8") (pintype "passive"))
      (node (ref "Q2") (pin "1") (pinfunction "E_1") (pintype "passive"))
      (node (ref "R16") (pin "1") (pintype "passive"))
      (node (ref "R17") (pin "1") (pintype "passive"))
      (node (ref "R23") (pin "2") (pintype "passive"))
      (node (ref "R26") (pin "2") (pintype "passive"))
      (node (ref "R27") (pin "2") (pintype "passive"))
      (node (ref "R28") (pin "2") (pintype "passive"))
      (node (ref "R29") (pin "2") (pintype "passive"))
      (node (ref "R3") (pin "1") (pintype "passive"))
      (node (ref "R30") (pin "2") (pintype "passive"))
      (node (ref "R43") (pin "2") (pintype "passive"))
      (node (ref "SD_CARD") (pin "4") (pinfunction "VCC_4") (pintype "bidirectional"))
      (node (ref "SWD") (pin "1") (pinfunction "1_1") (pintype "passive"))
      (node (ref "TFTLCD") (pin "24") (pinfunction "VDD3.3_24") (pintype "passive"))
      (node (ref "TFTLCD") (pin "25") (pinfunction "VDD3.3_25") (pintype "passive"))
      (node (ref "U1") (pin "100") (pinfunction "VDD_3_100") (pintype "bidirectional"))
      (node (ref "U1") (pin "11") (pinfunction "VDD_5_11") (pintype "bidirectional"))
      (node (ref "U1") (pin "28") (pinfunction "VDD_4_28") (pintype "bidirectional"))
      (node (ref "U1") (pin "50") (pinfunction "VDD_1_50") (pintype "bidirectional"))
      (node (ref "U1") (pin "75") (pinfunction "VDD_2_75") (pintype "bidirectional"))
      (node (ref "U2") (pin "2") (pinfunction "OUT_2") (pintype "passive"))
      (node (ref "U2") (pin "4") (pinfunction "OUT_4") (pintype "passive"))
      (node (ref "U4") (pin "3") (pinfunction "WP#_3") (pintype "passive"))
      (node (ref "U4") (pin "7") (pinfunction "HOLD_7") (pintype "passive"))
      (node (ref "U4") (pin "8") (pinfunction "VCC_8") (pintype "passive"))
      (node (ref "U5") (pin "9") (pinfunction "VDDIO_9") (pintype "passive"))
    )
    (net (code "91") (name "3V3_E") (class "Default")
      (node (ref "C32") (pin "2") (pintype "passive"))
      (node (ref "C33") (pin "2") (pintype "passive"))
      (node (ref "C40") (pin "2") (pintype "passive"))
      (node (ref "C42") (pin "2") (pintype "passive"))
      (node (ref "EARTHNET") (pin "4") (pinfunction "TCT_4") (pintype "passive"))
      (node (ref "EARTHNET") (pin "5") (pinfunction "RCT_5") (pintype "passive"))
      (node (ref "L1") (pin "1") (pintype "passive"))
      (node (ref "R34") (pin "2") (pintype "passive"))
      (node (ref "R35") (pin "2") (pintype "passive"))
      (node (ref "R36") (pin "2") (pintype "passive"))
      (node (ref "R37") (pin "2") (pintype "passive"))
      (node (ref "U5") (pin "1") (pinfunction "VDD2A_1") (pintype "passive"))
      (node (ref "U5") (pin "19") (pinfunction "VDD1A_19") (pintype "passive"))
    )
    (net (code "92") (name "5V") (class "Default")
      (node (ref "C19") (pin "1") (pintype "passive"))
      (node (ref "C22") (pin "2") (pintype "passive"))
      (node (ref "C23") (pin "1") (pintype "passive"))
      (node (ref "C43") (pin "2") (pintype "passive"))
      (node (ref "C44") (pin "2") (pintype "passive"))
      (node (ref "C45") (pin "1") (pintype "passive"))
      (node (ref "K1") (pin "2") (pinfunction "TAP1_2") (pintype "passive"))
      (node (ref "K1") (pin "5") (pinfunction "TAP2_5") (pintype "passive"))
      (node (ref "P1") (pin "2") (pinfunction "2_2") (pintype "passive"))
      (node (ref "P2") (pin "1") (pinfunction "1_1") (pintype "passive"))
      (node (ref "P2") (pin "2") (pinfunction "2_2") (pintype "passive"))
      (node (ref "R19") (pin "2") (pintype "passive"))
      (node (ref "TFTLCD") (pin "28") (pinfunction "BL_VDD_28") (pintype "passive"))
      (node (ref "U2") (pin "3") (pinfunction "IN_3") (pintype "passive"))
      (node (ref "U3") (pin "16") (pinfunction "VCC_16") (pintype "passive"))
    )
    (net (code "93") (name "GND") (class "Default")
      (node (ref "BAT") (pin "2") (pinfunction "GND_2") (pintype "passive"))
      (node (ref "BOOT") (pin "5") (pinfunction "5_5") (pintype "passive"))
      (node (ref "BOOT") (pin "6") (pinfunction "6_6") (pintype "passive"))
      (node (ref "C10") (pin "2") (pintype "passive"))
      (node (ref "C11") (pin "1") (pintype "passive"))
      (node (ref "C12") (pin "1") (pintype "passive"))
      (node (ref "C13") (pin "1") (pintype "passive"))
      (node (ref "C14") (pin "1") (pintype "passive"))
      (node (ref "C15") (pin "1") (pintype "passive"))
      (node (ref "C16") (pin "1") (pintype "passive"))
      (node (ref "C19") (pin "2") (pintype "passive"))
      (node (ref "C20") (pin "2") (pinfunction "GND_2") (pintype "passive"))
      (node (ref "C21") (pin "1") (pintype "passive"))
      (node (ref "C22") (pin "1") (pintype "passive"))
      (node (ref "C23") (pin "2") (pintype "passive"))
      (node (ref "C24") (pin "1") (pintype "passive"))
      (node (ref "C25") (pin "1") (pintype "passive"))
      (node (ref "C26") (pin "1") (pintype "passive"))
      (node (ref "C27") (pin "2") (pintype "passive"))
      (node (ref "C28") (pin "1") (pintype "passive"))
      (node (ref "C29") (pin "1") (pintype "passive"))
      (node (ref "C3") (pin "1") (pintype "passive"))
      (node (ref "C30") (pin "1") (pintype "passive"))
      (node (ref "C31") (pin "1") (pintype "passive"))
      (node (ref "C32") (pin "1") (pintype "passive"))
      (node (ref "C33") (pin "1") (pintype "passive"))
      (node (ref "C34") (pin "2") (pintype "passive"))
      (node (ref "C35") (pin "2") (pintype "passive"))
      (node (ref "C36") (pin "1") (pintype "passive"))
      (node (ref "C37") (pin "1") (pintype "passive"))
      (node (ref "C38") (pin "1") (pintype "passive"))
      (node (ref "C39") (pin "1") (pintype "passive"))
      (node (ref "C4") (pin "1") (pintype "passive"))
      (node (ref "C40") (pin "1") (pintype "passive"))
      (node (ref "C41") (pin "1") (pintype "passive"))
      (node (ref "C42") (pin "1") (pintype "passive"))
      (node (ref "C43") (pin "1") (pintype "passive"))
      (node (ref "C44") (pin "1") (pintype "passive"))
      (node (ref "C45") (pin "2") (pintype "passive"))
      (node (ref "C46") (pin "2") (pintype "passive"))
      (node (ref "C5") (pin "1") (pintype "passive"))
      (node (ref "C6") (pin "1") (pintype "passive"))
      (node (ref "C7") (pin "1") (pintype "passive"))
      (node (ref "C8") (pin "1") (pintype "passive"))
      (node (ref "C9") (pin "2") (pintype "passive"))
      (node (ref "DS1") (pin "2") (pinfunction "K_2") (pintype "passive"))
      (node (ref "EARTHNET") (pin "13") (pinfunction "SHILED_13") (pintype "passive"))
      (node (ref "EARTHNET") (pin "14") (pinfunction "SHILED_14") (pintype "passive"))
      (node (ref "EARTHNET") (pin "8") (pinfunction "CHS_GND_8") (pintype "passive"))
      (node (ref "P1") (pin "20") (pinfunction "20_20") (pintype "passive"))
      (node (ref "P2") (pin "3") (pinfunction "3_3") (pintype "passive"))
      (node (ref "P2") (pin "4") (pinfunction "4_4") (pintype "passive"))
      (node (ref "P2") (pin "5") (pinfunction "5_5") (pintype "passive"))
      (node (ref "P2") (pin "6") (pinfunction "6_6") (pintype "passive"))
      (node (ref "R18") (pin "1") (pintype "passive"))
      (node (ref "R2") (pin "1") (pintype "passive"))
      (node (ref "R32") (pin "1") (pintype "passive"))
      (node (ref "R33") (pin "1") (pintype "passive"))
      (node (ref "R38") (pin "2") (pintype "passive"))
      (node (ref "R39") (pin "2") (pintype "passive"))
      (node (ref "R41") (pin "1") (pintype "passive"))
      (node (ref "R42") (pin "1") (pintype "passive"))
      (node (ref "RESET") (pin "2") (pinfunction "2_2") (pintype "passive"))
      (node (ref "SD_CARD") (pin "6") (pinfunction "GND_6") (pintype "bidirectional"))
      (node (ref "SD_CARD") (pin "9") (pinfunction "NC_9") (pintype "bidirectional"))
      (node (ref "SWD") (pin "4") (pinfunction "4_4") (pintype "passive"))
      (node (ref "TFTLCD") (pin "22") (pinfunction "GND_22") (pintype "passive"))
      (node (ref "TFTLCD") (pin "26") (pinfunction "GND_26") (pintype "passive"))
      (node (ref "TFTLCD") (pin "27") (pinfunction "GND_27") (pintype "passive"))
      (node (ref "U1") (pin "10") (pinfunction "VSS_5_10") (pintype "bidirectional"))
      (node (ref "U1") (pin "27") (pinfunction "VSS_4_27") (pintype "bidirectional"))
      (node (ref "U1") (pin "74") (pinfunction "VSS_2_74") (pintype "bidirectional"))
      (node (ref "U1") (pin "99") (pinfunction "VSS_3_99") (pintype "bidirectional"))
      (node (ref "U2") (pin "1") (pinfunction "GND_1") (pintype "passive"))
      (node (ref "U3") (pin "1") (pinfunction "GND_1") (pintype "passive"))
      (node (ref "U4") (pin "4") (pinfunction "GND_4") (pintype "passive"))
      (node (ref "U5") (pin "25") (pinfunction "GND_25") (pintype "passive"))
      (node (ref "USB_SLAVE") (pin "5") (pinfunction "GND_5") (pintype "passive"))
    )
    (net (code "94") (name "Net-(BAT-VCC)") (class "Default")
      (node (ref "BAT") (pin "1") (pinfunction "VCC_1") (pintype "passive"))
      (node (ref "D2") (pin "1") (pinfunction "A_1") (pintype "passive"))
    )
    (net (code "95") (name "Net-(BOOT-Pad3)") (class "Default")
      (node (ref "BOOT") (pin "3") (pinfunction "3_3") (pintype "passive"))
      (node (ref "R5") (pin "2") (pintype "passive"))
    )
    (net (code "96") (name "Net-(BOOT-Pad4)") (class "Default")
      (node (ref "BOOT") (pin "4") (pinfunction "4_4") (pintype "passive"))
      (node (ref "R6") (pin "1") (pintype "passive"))
    )
    (net (code "97") (name "Net-(D3-K)") (class "Default")
      (node (ref "D3") (pin "2") (pinfunction "K_2") (pintype "passive"))
      (node (ref "Q1") (pin "3") (pinfunction "C_3") (pintype "passive"))
      (node (ref "R23") (pin "1") (pintype "passive"))
    )
    (net (code "98") (name "Net-(DS1-A)") (class "Default")
      (node (ref "DS1") (pin "1") (pinfunction "A_1") (pintype "passive"))
      (node (ref "R19") (pin "1") (pintype "passive"))
    )
    (net (code "99") (name "Net-(EARTHNET-LED(G)_K)") (class "Default")
      (node (ref "EARTHNET") (pin "10") (pinfunction "LED(G)_K_10") (pintype "passive"))
      (node (ref "R42") (pin "2") (pintype "passive"))
    )
    (net (code "100") (name "Net-(EARTHNET-LED(Y)_K)") (class "Default")
      (node (ref "EARTHNET") (pin "11") (pinfunction "LED(Y)_K_11") (pintype "passive"))
      (node (ref "R41") (pin "2") (pintype "passive"))
    )
    (net (code "101") (name "Net-(Q1-B)") (class "Default")
      (node (ref "Q1") (pin "2") (pinfunction "B_2") (pintype "passive"))
      (node (ref "R22") (pin "2") (pintype "passive"))
    )
    (net (code "102") (name "Net-(Q1-E)") (class "Default")
      (node (ref "Q1") (pin "1") (pinfunction "E_1") (pintype "passive"))
      (node (ref "R24") (pin "1") (pintype "passive"))
      (node (ref "U3") (pin "14") (pinfunction "RTS#_14") (pintype "passive"))
    )
    (net (code "103") (name "Net-(Q2-B)") (class "Default")
      (node (ref "Q2") (pin "2") (pinfunction "B_2") (pintype "passive"))
      (node (ref "R24") (pin "2") (pintype "passive"))
    )
    (net (code "104") (name "Net-(Q2-C)") (class "Default")
      (node (ref "Q2") (pin "3") (pinfunction "C_3") (pintype "passive"))
      (node (ref "R25") (pin "2") (pintype "passive"))
    )
    (net (code "105") (name "Net-(U1-OSC_IN)") (class "Default")
      (node (ref "C10") (pin "1") (pintype "passive"))
      (node (ref "R4") (pin "1") (pintype "passive"))
      (node (ref "U1") (pin "12") (pinfunction "OSC_IN_12") (pintype "bidirectional"))
      (node (ref "Y1") (pin "1") (pinfunction "OSC1_1") (pintype "passive"))
    )
    (net (code "106") (name "Net-(U1-OSC_OUT)") (class "Default")
      (node (ref "C9") (pin "1") (pintype "passive"))
      (node (ref "R4") (pin "2") (pintype "passive"))
      (node (ref "U1") (pin "13") (pinfunction "OSC_OUT_13") (pintype "bidirectional"))
      (node (ref "Y1") (pin "2") (pinfunction "OSC2_2") (pintype "passive"))
    )
    (net (code "107") (name "Net-(U1-PC14)") (class "Default")
      (node (ref "C14") (pin "2") (pintype "passive"))
      (node (ref "U1") (pin "8") (pinfunction "PC14_8") (pintype "bidirectional"))
      (node (ref "Y2") (pin "2") (pinfunction "OSC2_2") (pintype "passive"))
    )
    (net (code "108") (name "Net-(U1-PC15)") (class "Default")
      (node (ref "C13") (pin "2") (pintype "passive"))
      (node (ref "U1") (pin "9") (pinfunction "PC15_9") (pintype "bidirectional"))
      (node (ref "Y2") (pin "1") (pinfunction "OSC1_1") (pintype "passive"))
    )
    (net (code "109") (name "Net-(U1-VCAP_1)") (class "Default")
      (node (ref "C12") (pin "2") (pintype "passive"))
      (node (ref "U1") (pin "49") (pinfunction "VCAP_1_49") (pintype "bidirectional"))
    )
    (net (code "110") (name "Net-(U1-VCAP_2)") (class "Default")
      (node (ref "C11") (pin "2") (pintype "passive"))
      (node (ref "U1") (pin "73") (pinfunction "VCAP_2_73") (pintype "bidirectional"))
    )
    (net (code "111") (name "Net-(U1-VREF+)") (class "Default")
      (node (ref "R1") (pin "2") (pintype "passive"))
      (node (ref "U1") (pin "21") (pinfunction "VREF+_21") (pintype "bidirectional"))
    )
    (net (code "112") (name "Net-(U1-VREF-)") (class "Default")
      (node (ref "C1") (pin "1") (pintype "passive"))
      (node (ref "C2") (pin "1") (pintype "passive"))
      (node (ref "R2") (pin "2") (pintype "passive"))
      (node (ref "U1") (pin "20") (pinfunction "VREF-_20") (pintype "bidirectional"))
    )
    (net (code "113") (name "Net-(U3-DTR#)") (class "Default")
      (node (ref "R22") (pin "1") (pintype "passive"))
      (node (ref "U3") (pin "13") (pinfunction "DTR#_13") (pintype "passive"))
    )
    (net (code "114") (name "Net-(U3-V3)") (class "Default")
      (node (ref "C24") (pin "2") (pintype "passive"))
      (node (ref "U3") (pin "4") (pinfunction "V3_4") (pintype "passive"))
    )
    (net (code "115") (name "Net-(U3-XI)") (class "Default")
      (node (ref "C25") (pin "2") (pintype "passive"))
      (node (ref "U3") (pin "7") (pinfunction "XI_7") (pintype "passive"))
      (node (ref "Y3") (pin "1") (pinfunction "OSC1_1") (pintype "passive"))
    )
    (net (code "116") (name "Net-(U3-XO)") (class "Default")
      (node (ref "C26") (pin "2") (pintype "passive"))
      (node (ref "U3") (pin "8") (pinfunction "XO_8") (pintype "passive"))
      (node (ref "Y3") (pin "2") (pinfunction "OSC2_2") (pintype "passive"))
    )
    (net (code "117") (name "Net-(U5-MDIO)") (class "Default")
      (node (ref "R31") (pin "2") (pintype "passive"))
      (node (ref "U5") (pin "12") (pinfunction "MDIO_12") (pintype "passive"))
    )
    (net (code "118") (name "Net-(U5-RBIAS)") (class "Default")
      (node (ref "R32") (pin "2") (pintype "passive"))
      (node (ref "U5") (pin "24") (pinfunction "RBIAS_24") (pintype "passive"))
    )
    (net (code "119") (name "Net-(U5-VDDCR)") (class "Default")
      (node (ref "C29") (pin "2") (pintype "passive"))
      (node (ref "C30") (pin "2") (pintype "passive"))
      (node (ref "U5") (pin "6") (pinfunction "VDDCR_6") (pintype "passive"))
    )
    (net (code "120") (name "Net-(U5-XTAL1{slash}CLKIN)") (class "Default")
      (node (ref "C35") (pin "1") (pintype "passive"))
      (node (ref "R40") (pin "2") (pintype "passive"))
      (node (ref "U5") (pin "5") (pinfunction "XTAL1/CLKIN_5") (pintype "passive"))
      (node (ref "Y4") (pin "2") (pinfunction "OSC2_2") (pintype "passive"))
    )
    (net (code "121") (name "Net-(U5-XTAL2)") (class "Default")
      (node (ref "C34") (pin "1") (pintype "passive"))
      (node (ref "R40") (pin "1") (pintype "passive"))
      (node (ref "U5") (pin "4") (pinfunction "XTAL2_4") (pintype "passive"))
      (node (ref "Y4") (pin "1") (pinfunction "OSC1_1") (pintype "passive"))
    )
    (net (code "122") (name "VCC") (class "Default")
      (node (ref "C3") (pin "2") (pintype "passive"))
      (node (ref "C4") (pin "2") (pintype "passive"))
      (node (ref "C5") (pin "2") (pintype "passive"))
      (node (ref "C6") (pin "2") (pintype "passive"))
      (node (ref "C7") (pin "2") (pintype "passive"))
      (node (ref "C8") (pin "2") (pintype "passive"))
    )
    (net (code "123") (name "VDDA") (class "Default")
      (node (ref "C1") (pin "2") (pintype "passive"))
      (node (ref "C2") (pin "2") (pintype "passive"))
      (node (ref "R1") (pin "1") (pintype "passive"))
      (node (ref "R3") (pin "2") (pintype "passive"))
      (node (ref "U1") (pin "19") (pinfunction "VDD_19") (pintype "bidirectional"))
      (node (ref "U1") (pin "22") (pinfunction "VDDA_22") (pintype "bidirectional"))
    )
    (net (code "124") (name "VUSB") (class "Default")
      (node (ref "K1") (pin "3") (pinfunction "I/O1_3") (pintype "passive"))
      (node (ref "K1") (pin "4") (pinfunction "I/O2_4") (pintype "passive"))
      (node (ref "USB_SLAVE") (pin "1") (pinfunction "VCC_1") (pintype "passive"))
    )
    (net (code "125") (name "unconnected-(EARTHNET-NC-Pad7)") (class "Default")
      (node (ref "EARTHNET") (pin "7") (pinfunction "NC_7") (pintype "passive+no_connect"))
    )
    (net (code "126") (name "unconnected-(K1-I{slash}O1-Pad1)") (class "Default")
      (node (ref "K1") (pin "1") (pinfunction "I/O1_1") (pintype "passive+no_connect"))
    )
    (net (code "127") (name "unconnected-(K1-I{slash}O2-Pad6)") (class "Default")
      (node (ref "K1") (pin "6") (pinfunction "I/O2_6") (pintype "passive+no_connect"))
    )
    (net (code "128") (name "unconnected-(P1-Pad8)") (class "Default")
      (node (ref "P1") (pin "8") (pinfunction "8_8") (pintype "passive+no_connect"))
    )
    (net (code "129") (name "unconnected-(P1-Pad14)") (class "Default")
      (node (ref "P1") (pin "14") (pinfunction "14_14") (pintype "passive+no_connect"))
    )
    (net (code "130") (name "unconnected-(P1-Pad16)") (class "Default")
      (node (ref "P1") (pin "16") (pinfunction "16_16") (pintype "passive+no_connect"))
    )
    (net (code "131") (name "unconnected-(TFTLCD-MO-Pad32)") (class "Default")
      (node (ref "TFTLCD") (pin "32") (pinfunction "MO_32") (pintype "passive+no_connect"))
    )
    (net (code "132") (name "unconnected-(U3-CTS#-Pad9)") (class "Default")
      (node (ref "U3") (pin "9") (pinfunction "CTS#_9") (pintype "passive+no_connect"))
    )
    (net (code "133") (name "unconnected-(U3-DCD#-Pad12)") (class "Default")
      (node (ref "U3") (pin "12") (pinfunction "DCD#_12") (pintype "passive+no_connect"))
    )
    (net (code "134") (name "unconnected-(U3-DSR#-Pad10)") (class "Default")
      (node (ref "U3") (pin "10") (pinfunction "DSR#_10") (pintype "passive+no_connect"))
    )
    (net (code "135") (name "unconnected-(U3-R232-Pad15)") (class "Default")
      (node (ref "U3") (pin "15") (pinfunction "R232_15") (pintype "passive+no_connect"))
    )
    (net (code "136") (name "unconnected-(U3-RI#-Pad11)") (class "Default")
      (node (ref "U3") (pin "11") (pinfunction "RI#_11") (pintype "passive+no_connect"))
    )
    (net (code "137") (name "unconnected-(U5-RXER{slash}PHYAD0-Pad10)") (class "Default")
      (node (ref "U5") (pin "10") (pinfunction "RXER/PHYAD0_10") (pintype "passive+no_connect"))
    )
    (net (code "138") (name "unconnected-(USB_SLAVE-NC-Pad4)") (class "Default")
      (node (ref "USB_SLAVE") (pin "4") (pinfunction "NC_4") (pintype "passive+no_connect"))
    )
  )
)
